# gps.net
KiCad netlist of a schematic drawn in Altium Designer
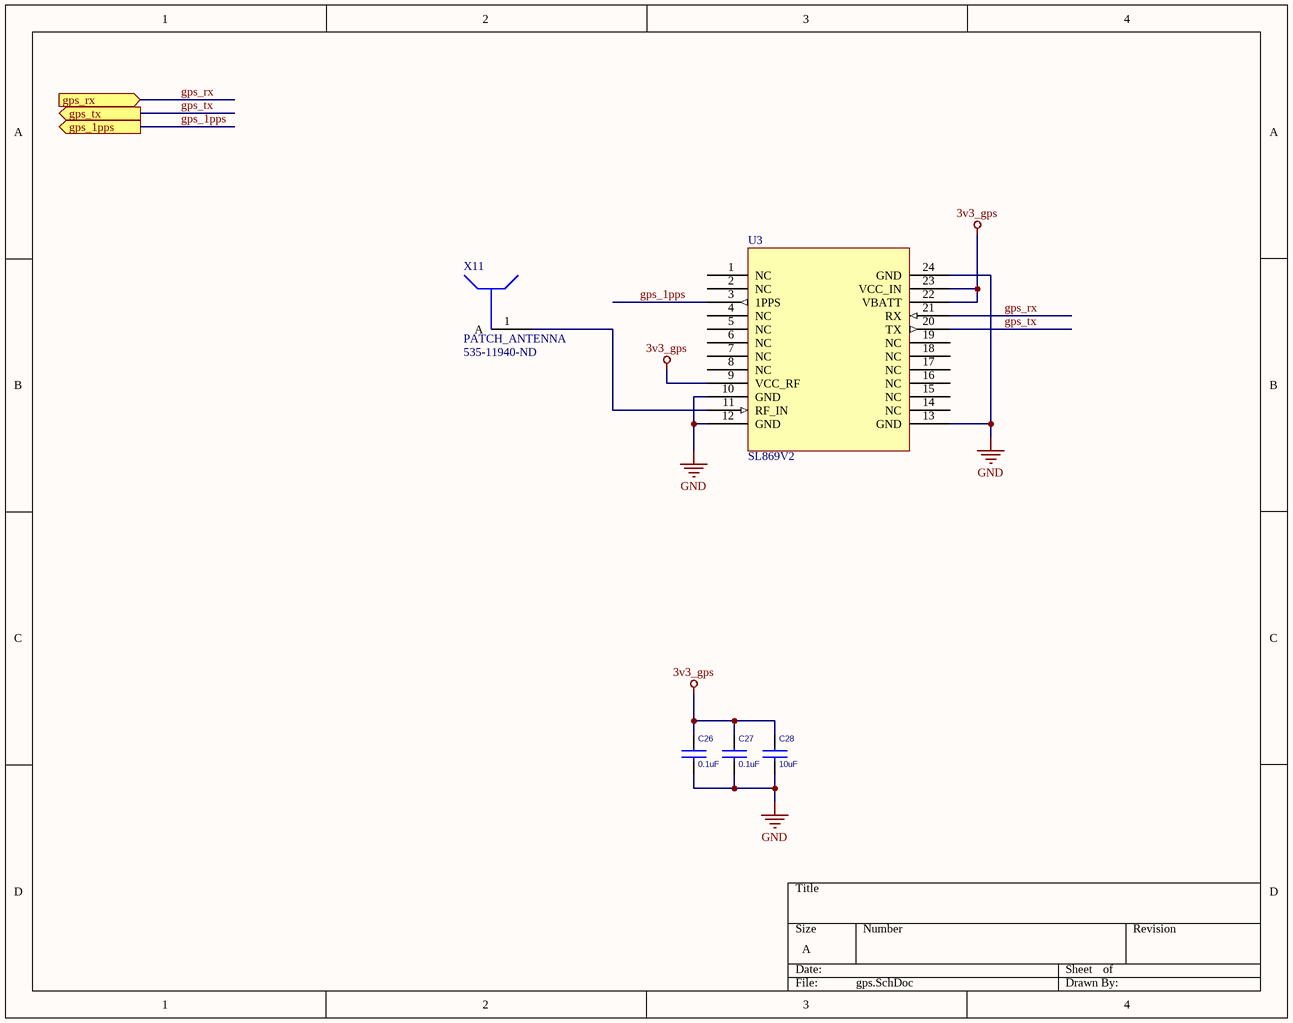
[diagram p0: gps.SchDoc]

(export (version "E")
  (design (tool "Eeschema 10.0.6"))
  (components
    (comp (ref "C26")
      (value "0.1uF")
      (footprint "CAPC2012X09M")
      (description "CAP CER 0.1UF 25V 10% X7R 0805")
      (libsource (lib "Capacitors") (part "CAP_SMD_0.1UF_10%"))
    )
    (comp (ref "C27")
      (value "0.1uF")
      (footprint "CAPC2012X09M")
      (description "CAP CER 0.1UF 25V 10% X7R 0805")
      (libsource (lib "Capacitors") (part "CAP_SMD_0.1UF_10%"))
    )
    (comp (ref "C28")
      (value "10uF")
      (footprint "CAPC2012X09M")
      (description "CAP CER 10UF 16V 20% X5R 0805")
      (libsource (lib "Capacitors") (part "CAP_SMD_10UF_20%"))
    )
    (comp (ref "U3")
      (value "SL869V2")
      (footprint "SL869V2_FOOT")
      (libsource (lib "TruthEar") (part "SL869V2"))
    )
    (comp (ref "X11")
      (value "PATCH_ANTENNA")
      (footprint "PATCH_ANTENNA")
      (fields (field (name "SUPPLIER PART NUMBER 1") "535-11940-ND"))
      (libsource (lib "TruthEar") (part "PATCH_ANTENNA"))
    )
  )
  (nets
    (net (code "1") (name "/gps_1pps") (class "Default")
      (node (ref "U3") (pin "3") (pinfunction "1PPS_3") (pintype "output"))
    )
    (net (code "2") (name "/gps_rx") (class "Default")
      (node (ref "U3") (pin "21") (pinfunction "RX_21") (pintype "input"))
    )
    (net (code "3") (name "/gps_tx") (class "Default")
      (node (ref "U3") (pin "20") (pinfunction "TX_20") (pintype "output"))
    )
    (net (code "4") (name "3v3_gps") (class "Default")
      (node (ref "C26") (pin "1") (pinfunction "1_1") (pintype "passive"))
      (node (ref "C27") (pin "1") (pinfunction "1_1") (pintype "passive"))
      (node (ref "C28") (pin "1") (pinfunction "1_1") (pintype "passive"))
      (node (ref "U3") (pin "22") (pinfunction "VBATT_22") (pintype "passive"))
      (node (ref "U3") (pin "23") (pinfunction "VCC_IN_23") (pintype "passive"))
      (node (ref "U3") (pin "9") (pinfunction "VCC_RF_9") (pintype "passive"))
    )
    (net (code "5") (name "GND") (class "Default")
      (node (ref "C26") (pin "2") (pinfunction "2_2") (pintype "passive"))
      (node (ref "C27") (pin "2") (pinfunction "2_2") (pintype "passive"))
      (node (ref "C28") (pin "2") (pinfunction "2_2") (pintype "passive"))
      (node (ref "U3") (pin "10") (pinfunction "GND_10") (pintype "passive"))
      (node (ref "U3") (pin "12") (pinfunction "GND_12") (pintype "passive"))
      (node (ref "U3") (pin "13") (pinfunction "GND_13") (pintype "passive"))
      (node (ref "U3") (pin "24") (pinfunction "GND_24") (pintype "passive"))
    )
    (net (code "6") (name "Net-(U3-RF_IN)") (class "Default")
      (node (ref "U3") (pin "11") (pinfunction "RF_IN_11") (pintype "input"))
      (node (ref "X11") (pin "1") (pinfunction "A_1") (pintype "passive"))
    )
    (net (code "7") (name "unconnected-(U3-NC-Pad1)") (class "Default")
      (node (ref "U3") (pin "1") (pinfunction "NC_1") (pintype "passive"))
    )
    (net (code "8") (name "unconnected-(U3-NC-Pad2)") (class "Default")
      (node (ref "U3") (pin "2") (pinfunction "NC_2") (pintype "passive"))
    )
    (net (code "9") (name "unconnected-(U3-NC-Pad4)") (class "Default")
      (node (ref "U3") (pin "4") (pinfunction "NC_4") (pintype "passive"))
    )
    (net (code "10") (name "unconnected-(U3-NC-Pad5)") (class "Default")
      (node (ref "U3") (pin "5") (pinfunction "NC_5") (pintype "passive"))
    )
    (net (code "11") (name "unconnected-(U3-NC-Pad6)") (class "Default")
      (node (ref "U3") (pin "6") (pinfunction "NC_6") (pintype "passive"))
    )
    (net (code "12") (name "unconnected-(U3-NC-Pad7)") (class "Default")
      (node (ref "U3") (pin "7") (pinfunction "NC_7") (pintype "passive"))
    )
    (net (code "13") (name "unconnected-(U3-NC-Pad8)") (class "Default")
      (node (ref "U3") (pin "8") (pinfunction "NC_8") (pintype "passive"))
    )
    (net (code "14") (name "unconnected-(U3-NC-Pad14)") (class "Default")
      (node (ref "U3") (pin "14") (pinfunction "NC_14") (pintype "passive"))
    )
    (net (code "15") (name "unconnected-(U3-NC-Pad15)") (class "Default")
      (node (ref "U3") (pin "15") (pinfunction "NC_15") (pintype "passive"))
    )
    (net (code "16") (name "unconnected-(U3-NC-Pad16)") (class "Default")
      (node (ref "U3") (pin "16") (pinfunction "NC_16") (pintype "passive"))
    )
    (net (code "17") (name "unconnected-(U3-NC-Pad17)") (class "Default")
      (node (ref "U3") (pin "17") (pinfunction "NC_17") (pintype "passive"))
    )
    (net (code "18") (name "unconnected-(U3-NC-Pad18)") (class "Default")
      (node (ref "U3") (pin "18") (pinfunction "NC_18") (pintype "passive"))
    )
    (net (code "19") (name "unconnected-(U3-NC-Pad19)") (class "Default")
      (node (ref "U3") (pin "19") (pinfunction "NC_19") (pintype "passive"))
    )
  )
)
